# phone_jack_breaklight_Seeed_OPL-with-pla.net
KiCad netlist of a schematic drawn in EAGLE
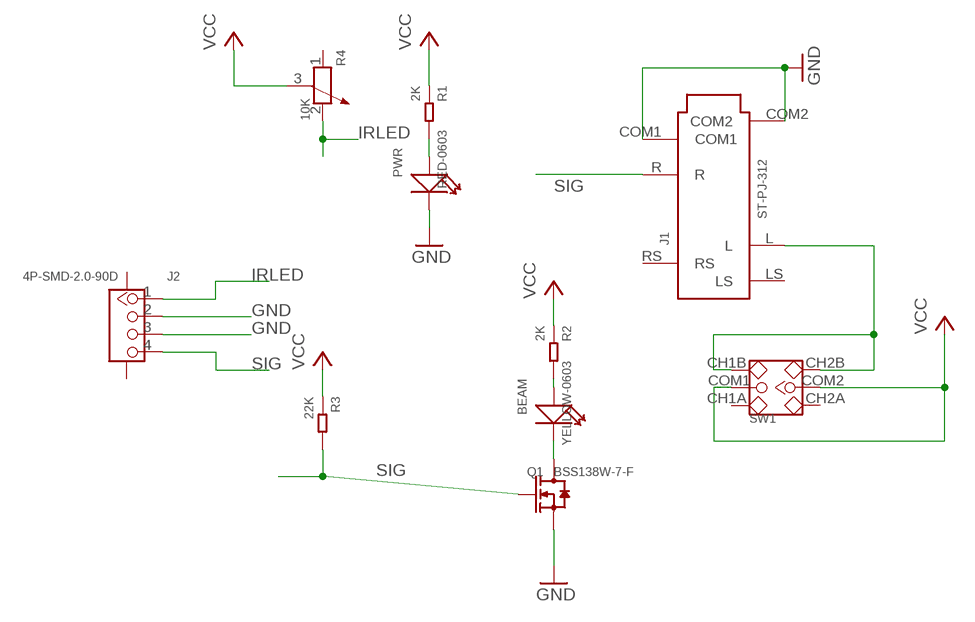
[diagram p0: schematic, sheet 1]

(export (version "E")
  (design (tool "Eeschema 10.0.6"))
  (components
    (comp (ref "J1")
      (value "ST-PJ-312")
      (footprint "eagle-import:AUDIO6P-SMD-3.5-14.0X6.4X5.0MM")
      (libsource (lib "eagle-import") (part "AUDIO-JACK-6P-SMD(ST-PJ-312)"))
    )
    (comp (ref "J2")
      (value "4P-SMD-2.0-90D")
      (footprint "eagle-import:HW4-SMD-2.0-90D")
      (libsource (lib "eagle-import") (part "GROVE-CONNECTOR-SMD-90D(4+2P-2.0)"))
    )
    (comp (ref "Q1")
      (value "BSS138W-7-F")
      (footprint "eagle-import:SOT-23")
      (libsource (lib "eagle-import") (part "SMD-MOSFET-N-CH-50V-200MA-BSS138W-7-F(SOT-23)"))
    )
    (comp (ref "R1")
      (value "2K")
      (footprint "eagle-import:R0603")
      (fields (field (name "MPN") "RC0603JR-072KL"))
      (libsource (lib "eagle-import") (part "SMD-RES-2K-5%-1/10W(0603)"))
    )
    (comp (ref "R2")
      (value "2K")
      (footprint "eagle-import:R0603")
      (fields (field (name "MPN") "RC0603JR-072KL"))
      (libsource (lib "eagle-import") (part "SMD-RES-2K-5%-1/10W(0603)"))
    )
    (comp (ref "R3")
      (value "22K")
      (footprint "eagle-import:R0603")
      (fields (field (name "MPN") "RC0603JR-0722KL"))
      (libsource (lib "eagle-import") (part "SMD-RES-22K-5%-1/10W(0603)"))
    )
    (comp (ref "R4")
      (value "10K")
      (footprint "eagle-import:ADJR3-9.5X9.5X10.5MM")
      (fields (field (name "MPN") "3386U-103"))
      (libsource (lib "eagle-import") (part "DIP-VR-TOP-ADJ-10K(3P-9.5X9.5X5MM)"))
    )
    (comp (ref "RED-0603")
      (value "PWR")
      (footprint "eagle-import:LED-0603")
      (fields (field (name "MPN") "19-217-R6C-AL1M2VY-3T"))
      (libsource (lib "eagle-import") (part "LED-SMD-RED-DIFFUSED(0603)"))
    )
    (comp (ref "SW1")
      (value "DIP-TOGGLE-SWITCH-2CH-(2X3P-2.54-90D)'90D'")
      (footprint "eagle-import:SW6-2.54-9.0X3.5X3.2MM-90D")
      (libsource (lib "eagle-import") (part "DIP-TOGGLE-SWITCH-2CH-(2X3P-2.54-90D)'90D'"))
    )
    (comp (ref "YELLOW-0603")
      (value "BEAM")
      (footprint "eagle-import:LED-0603")
      (fields (field (name "MPN") "19-217-Y5C-AM1N1VY-3T"))
      (libsource (lib "eagle-import") (part "SMD-LED-CLEAR-YELLOW(0603)"))
    )
  )
  (nets
    (net (code "1") (name "/IRLED") (class "Default")
      (node (ref "J2") (pin "1") (pinfunction "1_1") (pintype "bidirectional"))
      (node (ref "R4") (pin "2") (pinfunction "2_2") (pintype "passive"))
    )
    (net (code "2") (name "/SIG") (class "Default")
      (node (ref "J1") (pin "R") (pinfunction "R_R") (pintype "bidirectional"))
      (node (ref "J2") (pin "4") (pinfunction "4_4") (pintype "bidirectional"))
      (node (ref "Q1") (pin "1") (pinfunction "G_1") (pintype "passive"))
      (node (ref "R3") (pin "2") (pinfunction "2_2") (pintype "passive"))
    )
    (net (code "3") (name "GND") (class "Default")
      (node (ref "J1") (pin "COM1") (pinfunction "COM1_COM1") (pintype "bidirectional"))
      (node (ref "J1") (pin "COM2") (pinfunction "COM2_COM2") (pintype "bidirectional"))
      (node (ref "J2") (pin "2") (pinfunction "2_2") (pintype "bidirectional"))
      (node (ref "J2") (pin "3") (pinfunction "3_3") (pintype "bidirectional"))
      (node (ref "Q1") (pin "2") (pinfunction "S_2") (pintype "passive"))
      (node (ref "RED-0603") (pin "-") (pinfunction "-_-") (pintype "passive"))
    )
    (net (code "4") (name "Net-(J1-PadL)") (class "Default")
      (node (ref "J1") (pin "L") (pinfunction "L_L") (pintype "bidirectional"))
      (node (ref "SW1") (pin "CH1B") (pinfunction "CH1B_CH1B") (pintype "bidirectional"))
      (node (ref "SW1") (pin "CH2B") (pinfunction "CH2B_CH2B") (pintype "bidirectional"))
    )
    (net (code "5") (name "Net-(Q1-D)") (class "Default")
      (node (ref "Q1") (pin "3") (pinfunction "D_3") (pintype "passive"))
      (node (ref "YELLOW-0603") (pin "-") (pinfunction "-_-") (pintype "passive"))
    )
    (net (code "6") (name "Net-(R1-Pad2)") (class "Default")
      (node (ref "R1") (pin "2") (pinfunction "2_2") (pintype "passive"))
      (node (ref "RED-0603") (pin "+") (pinfunction "+_+") (pintype "passive"))
    )
    (net (code "7") (name "Net-(R2-Pad2)") (class "Default")
      (node (ref "R2") (pin "2") (pinfunction "2_2") (pintype "passive"))
      (node (ref "YELLOW-0603") (pin "+") (pinfunction "+_+") (pintype "passive"))
    )
    (net (code "8") (name "VCC") (class "Default")
      (node (ref "R1") (pin "1") (pinfunction "1_1") (pintype "passive"))
      (node (ref "R2") (pin "1") (pinfunction "1_1") (pintype "passive"))
      (node (ref "R3") (pin "1") (pinfunction "1_1") (pintype "passive"))
      (node (ref "R4") (pin "3") (pinfunction "3_3") (pintype "passive"))
      (node (ref "SW1") (pin "COM1") (pinfunction "COM1_COM1") (pintype "bidirectional"))
      (node (ref "SW1") (pin "COM2") (pinfunction "COM2_COM2") (pintype "bidirectional"))
    )
    (net (code "9") (name "unconnected-(J1-PadLS)") (class "Default")
      (node (ref "J1") (pin "LS") (pinfunction "LS_LS") (pintype "bidirectional"))
    )
    (net (code "10") (name "unconnected-(J1-PadRS)") (class "Default")
      (node (ref "J1") (pin "RS") (pinfunction "RS_RS") (pintype "bidirectional"))
    )
    (net (code "11") (name "unconnected-(J2-PadSS1)") (class "Default")
      (node (ref "J2") (pin "SS1") (pinfunction "SS1_SS1") (pintype "bidirectional"))
    )
    (net (code "12") (name "unconnected-(J2-PadSS2)") (class "Default")
      (node (ref "J2") (pin "SS2") (pinfunction "SS2_SS2") (pintype "bidirectional"))
    )
    (net (code "13") (name "unconnected-(R4-Pad1)") (class "Default")
      (node (ref "R4") (pin "1") (pinfunction "1_1") (pintype "passive"))
    )
    (net (code "14") (name "unconnected-(SW1-PadCH1A)") (class "Default")
      (node (ref "SW1") (pin "CH1A") (pinfunction "CH1A_CH1A") (pintype "bidirectional"))
    )
    (net (code "15") (name "unconnected-(SW1-PadCH2A)") (class "Default")
      (node (ref "SW1") (pin "CH2A") (pinfunction "CH2A_CH2A") (pintype "bidirectional"))
    )
  )
)
